# PS_DDR.net
KiCad netlist of a schematic drawn in Altium Designer
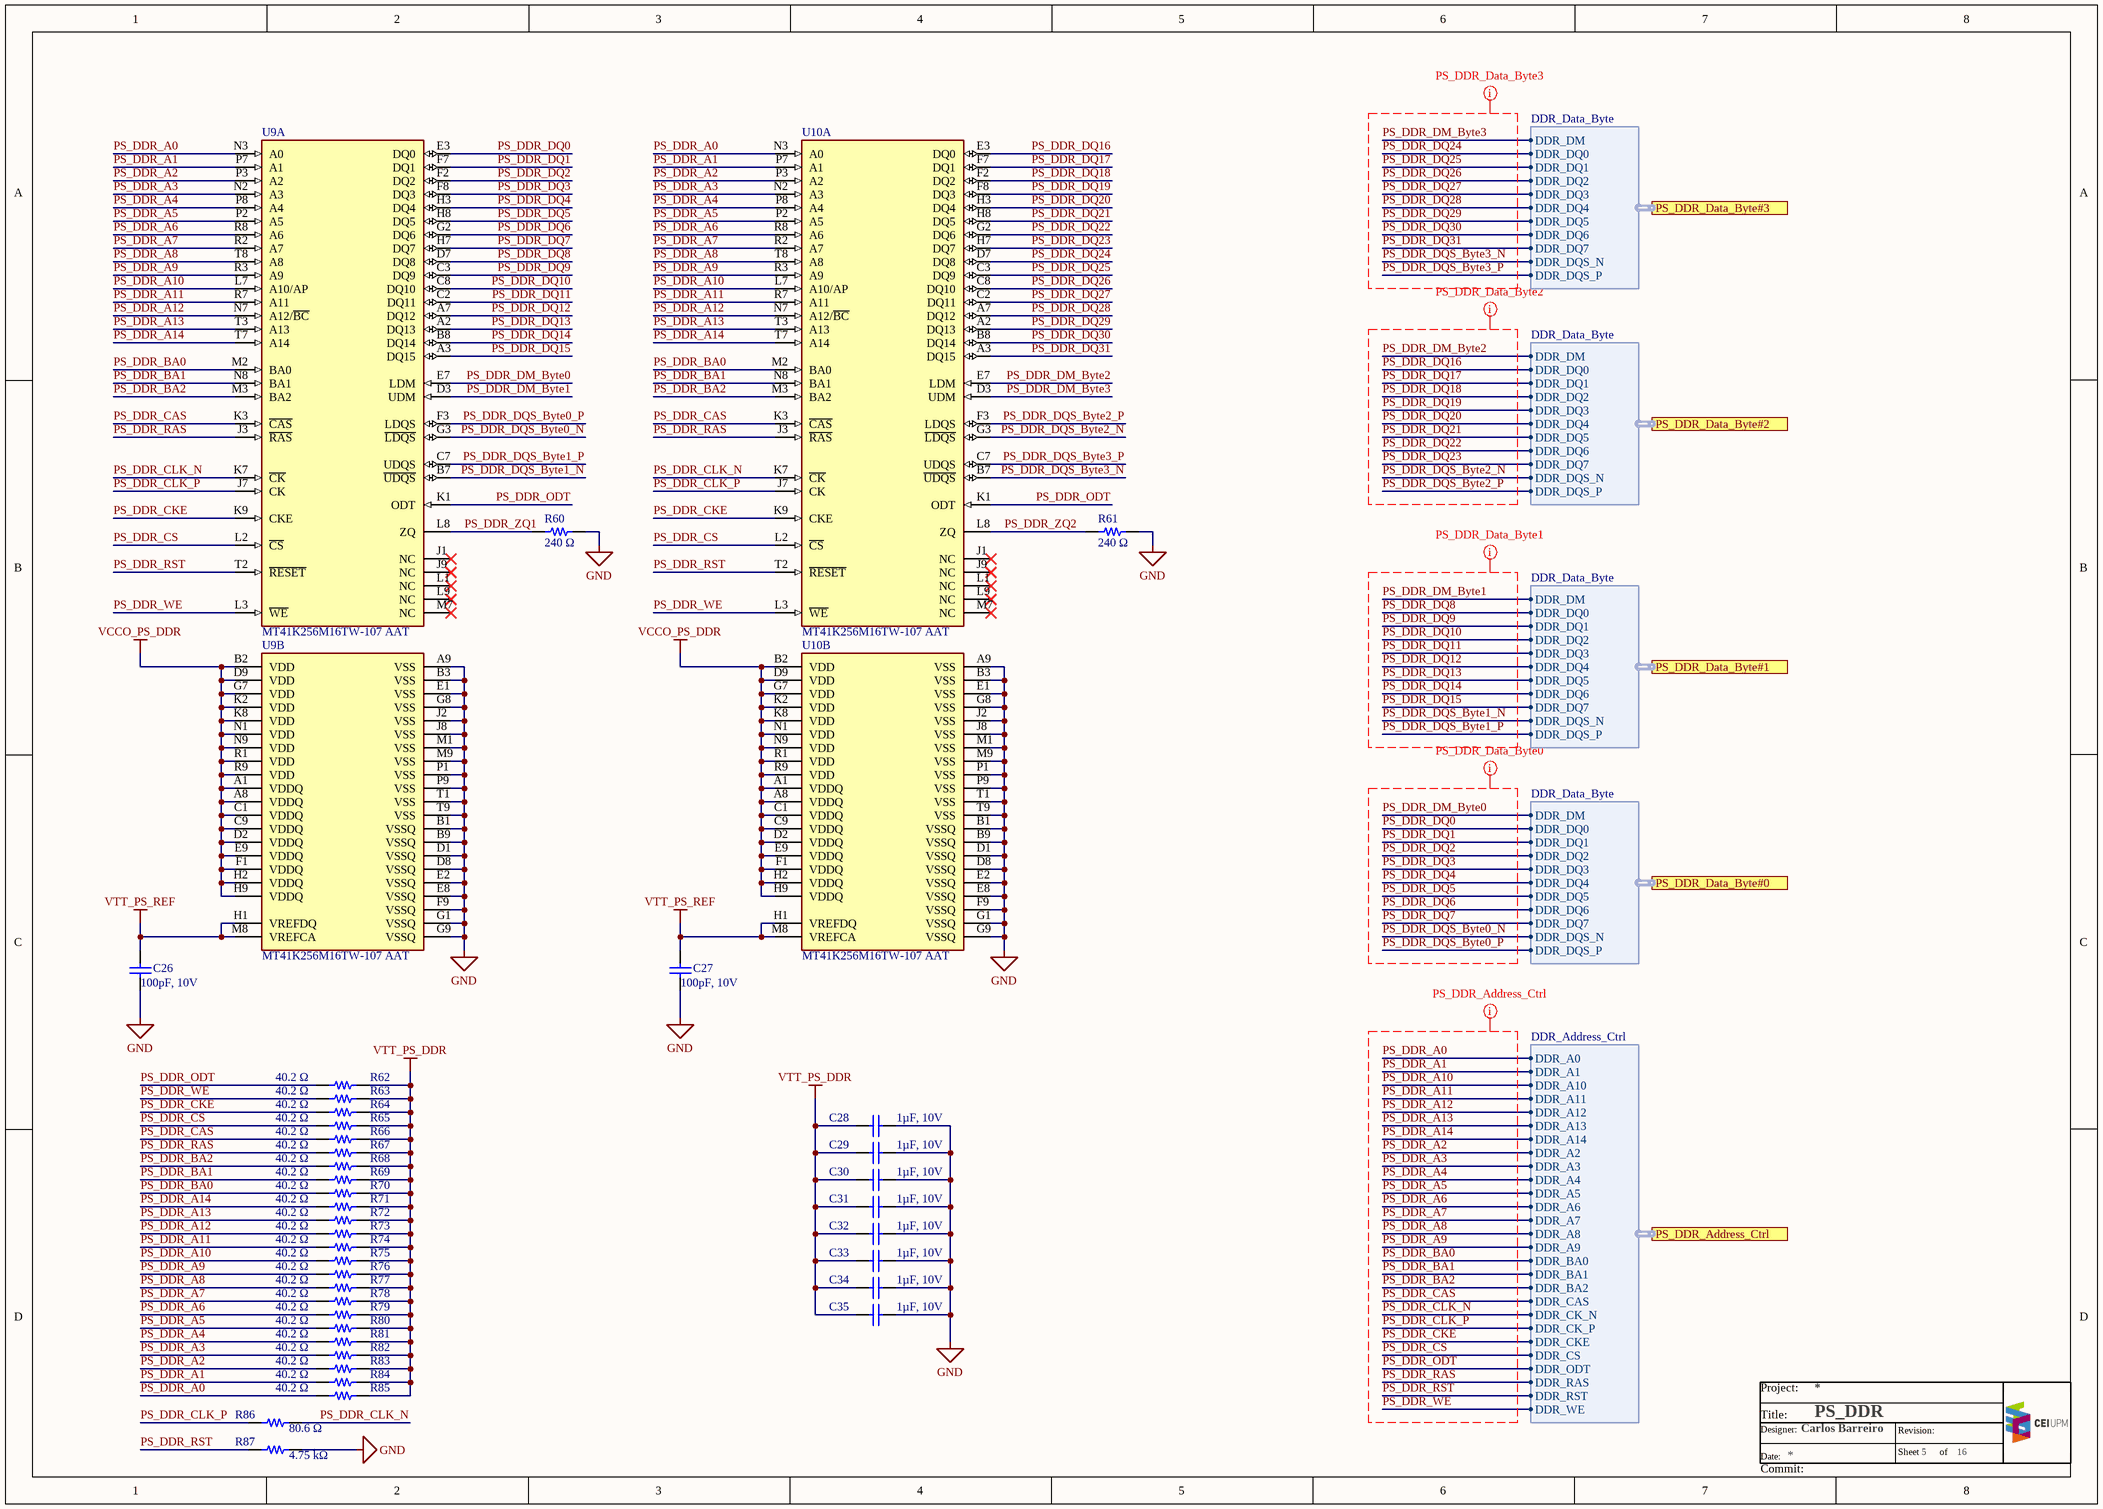
[diagram p0: PS_DDR.SchDoc]

(export (version "E")
  (design (tool "Eeschema 10.0.6"))
  (components
    (comp (ref "C26")
      (value "100pF, 10V")
      (footprint "WURTH_WCAP-CSGP_0402")
      (description "WCAP-CSGP Multilayer Ceramic Chip Capacitor, General Purpose, size 0402, NP0, 100pF, 10V")
      (fields
        (field (name "MANUFACTURER PART NUMBER") "885012005013")
        (field (name "MANUFACTURER") "Wurth Elektronik")
      )
      (libsource (lib "SpaceVNXBaseBoard") (part "885012005013"))
    )
    (comp (ref "C27")
      (value "100pF, 10V")
      (footprint "WURTH_WCAP-CSGP_0402")
      (description "WCAP-CSGP Multilayer Ceramic Chip Capacitor, General Purpose, size 0402, NP0, 100pF, 10V")
      (fields
        (field (name "MANUFACTURER PART NUMBER") "885012005013")
        (field (name "MANUFACTURER") "Wurth Elektronik")
      )
      (libsource (lib "SpaceVNXBaseBoard") (part "885012005013"))
    )
    (comp (ref "C28")
      (value "1µF, 10V")
      (footprint "WURTH_WCAP-CSGP_0402")
      (description "WCAP-CSGP Multilayer Ceramic Chip Capacitor, General Purpose, size 0402, X5R, 1uF, 10V")
      (fields
        (field (name "MANUFACTURER PART NUMBER") "885012105012")
        (field (name "MANUFACTURER") "Wurth Elektronik")
      )
      (libsource (lib "SpaceVNXBaseBoard") (part "885012105012"))
    )
    (comp (ref "C29")
      (value "1µF, 10V")
      (footprint "WURTH_WCAP-CSGP_0402")
      (description "WCAP-CSGP Multilayer Ceramic Chip Capacitor, General Purpose, size 0402, X5R, 1uF, 10V")
      (fields
        (field (name "MANUFACTURER PART NUMBER") "885012105012")
        (field (name "MANUFACTURER") "Wurth Elektronik")
      )
      (libsource (lib "SpaceVNXBaseBoard") (part "885012105012"))
    )
    (comp (ref "C30")
      (value "1µF, 10V")
      (footprint "WURTH_WCAP-CSGP_0402")
      (description "WCAP-CSGP Multilayer Ceramic Chip Capacitor, General Purpose, size 0402, X5R, 1uF, 10V")
      (fields
        (field (name "MANUFACTURER PART NUMBER") "885012105012")
        (field (name "MANUFACTURER") "Wurth Elektronik")
      )
      (libsource (lib "SpaceVNXBaseBoard") (part "885012105012"))
    )
    (comp (ref "C31")
      (value "1µF, 10V")
      (footprint "WURTH_WCAP-CSGP_0402")
      (description "WCAP-CSGP Multilayer Ceramic Chip Capacitor, General Purpose, size 0402, X5R, 1uF, 10V")
      (fields
        (field (name "MANUFACTURER PART NUMBER") "885012105012")
        (field (name "MANUFACTURER") "Wurth Elektronik")
      )
      (libsource (lib "SpaceVNXBaseBoard") (part "885012105012"))
    )
    (comp (ref "C32")
      (value "1µF, 10V")
      (footprint "WURTH_WCAP-CSGP_0402")
      (description "WCAP-CSGP Multilayer Ceramic Chip Capacitor, General Purpose, size 0402, X5R, 1uF, 10V")
      (fields
        (field (name "MANUFACTURER PART NUMBER") "885012105012")
        (field (name "MANUFACTURER") "Wurth Elektronik")
      )
      (libsource (lib "SpaceVNXBaseBoard") (part "885012105012"))
    )
    (comp (ref "C33")
      (value "1µF, 10V")
      (footprint "WURTH_WCAP-CSGP_0402")
      (description "WCAP-CSGP Multilayer Ceramic Chip Capacitor, General Purpose, size 0402, X5R, 1uF, 10V")
      (fields
        (field (name "MANUFACTURER PART NUMBER") "885012105012")
        (field (name "MANUFACTURER") "Wurth Elektronik")
      )
      (libsource (lib "SpaceVNXBaseBoard") (part "885012105012"))
    )
    (comp (ref "C34")
      (value "1µF, 10V")
      (footprint "WURTH_WCAP-CSGP_0402")
      (description "WCAP-CSGP Multilayer Ceramic Chip Capacitor, General Purpose, size 0402, X5R, 1uF, 10V")
      (fields
        (field (name "MANUFACTURER PART NUMBER") "885012105012")
        (field (name "MANUFACTURER") "Wurth Elektronik")
      )
      (libsource (lib "SpaceVNXBaseBoard") (part "885012105012"))
    )
    (comp (ref "C35")
      (value "1µF, 10V")
      (footprint "WURTH_WCAP-CSGP_0402")
      (description "WCAP-CSGP Multilayer Ceramic Chip Capacitor, General Purpose, size 0402, X5R, 1uF, 10V")
      (fields
        (field (name "MANUFACTURER PART NUMBER") "885012105012")
        (field (name "MANUFACTURER") "Wurth Elektronik")
      )
      (libsource (lib "SpaceVNXBaseBoard") (part "885012105012"))
    )
    (comp (ref "R60")
      (value "240 Ω")
      (footprint "PANASONIC_ERJ2G_0402")
      (description "General Purpose Thick Film Chip Resistors")
      (fields (field (name "MANUFACTURER") "Panasonic"))
      (libsource (lib "SpaceVNXBaseBoard") (part "ERJ2GEJ241X"))
    )
    (comp (ref "R61")
      (value "240 Ω")
      (footprint "PANASONIC_ERJ2G_0402")
      (description "General Purpose Thick Film Chip Resistors")
      (fields (field (name "MANUFACTURER") "Panasonic"))
      (libsource (lib "SpaceVNXBaseBoard") (part "ERJ2GEJ241X"))
    )
    (comp (ref "R62")
      (value "40.2 Ω")
      (footprint "PANASONIC_ERJ2G_0402")
      (description "General Purpose Thick Film Chip Resistors")
      (fields (field (name "MANUFACTURER") "Panasonic"))
      (libsource (lib "SpaceVNXBaseBoard") (part "ERJ2RKF40R2X"))
    )
    (comp (ref "R63")
      (value "40.2 Ω")
      (footprint "PANASONIC_ERJ2G_0402")
      (description "General Purpose Thick Film Chip Resistors")
      (fields (field (name "MANUFACTURER") "Panasonic"))
      (libsource (lib "SpaceVNXBaseBoard") (part "ERJ2RKF40R2X"))
    )
    (comp (ref "R64")
      (value "40.2 Ω")
      (footprint "PANASONIC_ERJ2G_0402")
      (description "General Purpose Thick Film Chip Resistors")
      (fields (field (name "MANUFACTURER") "Panasonic"))
      (libsource (lib "SpaceVNXBaseBoard") (part "ERJ2RKF40R2X"))
    )
    (comp (ref "R65")
      (value "40.2 Ω")
      (footprint "PANASONIC_ERJ2G_0402")
      (description "General Purpose Thick Film Chip Resistors")
      (fields (field (name "MANUFACTURER") "Panasonic"))
      (libsource (lib "SpaceVNXBaseBoard") (part "ERJ2RKF40R2X"))
    )
    (comp (ref "R66")
      (value "40.2 Ω")
      (footprint "PANASONIC_ERJ2G_0402")
      (description "General Purpose Thick Film Chip Resistors")
      (fields (field (name "MANUFACTURER") "Panasonic"))
      (libsource (lib "SpaceVNXBaseBoard") (part "ERJ2RKF40R2X"))
    )
    (comp (ref "R67")
      (value "40.2 Ω")
      (footprint "PANASONIC_ERJ2G_0402")
      (description "General Purpose Thick Film Chip Resistors")
      (fields (field (name "MANUFACTURER") "Panasonic"))
      (libsource (lib "SpaceVNXBaseBoard") (part "ERJ2RKF40R2X"))
    )
    (comp (ref "R68")
      (value "40.2 Ω")
      (footprint "PANASONIC_ERJ2G_0402")
      (description "General Purpose Thick Film Chip Resistors")
      (fields (field (name "MANUFACTURER") "Panasonic"))
      (libsource (lib "SpaceVNXBaseBoard") (part "ERJ2RKF40R2X"))
    )
    (comp (ref "R69")
      (value "40.2 Ω")
      (footprint "PANASONIC_ERJ2G_0402")
      (description "General Purpose Thick Film Chip Resistors")
      (fields (field (name "MANUFACTURER") "Panasonic"))
      (libsource (lib "SpaceVNXBaseBoard") (part "ERJ2RKF40R2X"))
    )
    (comp (ref "R70")
      (value "40.2 Ω")
      (footprint "PANASONIC_ERJ2G_0402")
      (description "General Purpose Thick Film Chip Resistors")
      (fields (field (name "MANUFACTURER") "Panasonic"))
      (libsource (lib "SpaceVNXBaseBoard") (part "ERJ2RKF40R2X"))
    )
    (comp (ref "R71")
      (value "40.2 Ω")
      (footprint "PANASONIC_ERJ2G_0402")
      (description "General Purpose Thick Film Chip Resistors")
      (fields (field (name "MANUFACTURER") "Panasonic"))
      (libsource (lib "SpaceVNXBaseBoard") (part "ERJ2RKF40R2X"))
    )
    (comp (ref "R72")
      (value "40.2 Ω")
      (footprint "PANASONIC_ERJ2G_0402")
      (description "General Purpose Thick Film Chip Resistors")
      (fields (field (name "MANUFACTURER") "Panasonic"))
      (libsource (lib "SpaceVNXBaseBoard") (part "ERJ2RKF40R2X"))
    )
    (comp (ref "R73")
      (value "40.2 Ω")
      (footprint "PANASONIC_ERJ2G_0402")
      (description "General Purpose Thick Film Chip Resistors")
      (fields (field (name "MANUFACTURER") "Panasonic"))
      (libsource (lib "SpaceVNXBaseBoard") (part "ERJ2RKF40R2X"))
    )
    (comp (ref "R74")
      (value "40.2 Ω")
      (footprint "PANASONIC_ERJ2G_0402")
      (description "General Purpose Thick Film Chip Resistors")
      (fields (field (name "MANUFACTURER") "Panasonic"))
      (libsource (lib "SpaceVNXBaseBoard") (part "ERJ2RKF40R2X"))
    )
    (comp (ref "R75")
      (value "40.2 Ω")
      (footprint "PANASONIC_ERJ2G_0402")
      (description "General Purpose Thick Film Chip Resistors")
      (fields (field (name "MANUFACTURER") "Panasonic"))
      (libsource (lib "SpaceVNXBaseBoard") (part "ERJ2RKF40R2X"))
    )
    (comp (ref "R76")
      (value "40.2 Ω")
      (footprint "PANASONIC_ERJ2G_0402")
      (description "General Purpose Thick Film Chip Resistors")
      (fields (field (name "MANUFACTURER") "Panasonic"))
      (libsource (lib "SpaceVNXBaseBoard") (part "ERJ2RKF40R2X"))
    )
    (comp (ref "R77")
      (value "40.2 Ω")
      (footprint "PANASONIC_ERJ2G_0402")
      (description "General Purpose Thick Film Chip Resistors")
      (fields (field (name "MANUFACTURER") "Panasonic"))
      (libsource (lib "SpaceVNXBaseBoard") (part "ERJ2RKF40R2X"))
    )
    (comp (ref "R78")
      (value "40.2 Ω")
      (footprint "PANASONIC_ERJ2G_0402")
      (description "General Purpose Thick Film Chip Resistors")
      (fields (field (name "MANUFACTURER") "Panasonic"))
      (libsource (lib "SpaceVNXBaseBoard") (part "ERJ2RKF40R2X"))
    )
    (comp (ref "R79")
      (value "40.2 Ω")
      (footprint "PANASONIC_ERJ2G_0402")
      (description "General Purpose Thick Film Chip Resistors")
      (fields (field (name "MANUFACTURER") "Panasonic"))
      (libsource (lib "SpaceVNXBaseBoard") (part "ERJ2RKF40R2X"))
    )
    (comp (ref "R80")
      (value "40.2 Ω")
      (footprint "PANASONIC_ERJ2G_0402")
      (description "General Purpose Thick Film Chip Resistors")
      (fields (field (name "MANUFACTURER") "Panasonic"))
      (libsource (lib "SpaceVNXBaseBoard") (part "ERJ2RKF40R2X"))
    )
    (comp (ref "R81")
      (value "40.2 Ω")
      (footprint "PANASONIC_ERJ2G_0402")
      (description "General Purpose Thick Film Chip Resistors")
      (fields (field (name "MANUFACTURER") "Panasonic"))
      (libsource (lib "SpaceVNXBaseBoard") (part "ERJ2RKF40R2X"))
    )
    (comp (ref "R82")
      (value "40.2 Ω")
      (footprint "PANASONIC_ERJ2G_0402")
      (description "General Purpose Thick Film Chip Resistors")
      (fields (field (name "MANUFACTURER") "Panasonic"))
      (libsource (lib "SpaceVNXBaseBoard") (part "ERJ2RKF40R2X"))
    )
    (comp (ref "R83")
      (value "40.2 Ω")
      (footprint "PANASONIC_ERJ2G_0402")
      (description "General Purpose Thick Film Chip Resistors")
      (fields (field (name "MANUFACTURER") "Panasonic"))
      (libsource (lib "SpaceVNXBaseBoard") (part "ERJ2RKF40R2X"))
    )
    (comp (ref "R84")
      (value "40.2 Ω")
      (footprint "PANASONIC_ERJ2G_0402")
      (description "General Purpose Thick Film Chip Resistors")
      (fields (field (name "MANUFACTURER") "Panasonic"))
      (libsource (lib "SpaceVNXBaseBoard") (part "ERJ2RKF40R2X"))
    )
    (comp (ref "R85")
      (value "40.2 Ω")
      (footprint "PANASONIC_ERJ2G_0402")
      (description "General Purpose Thick Film Chip Resistors")
      (fields (field (name "MANUFACTURER") "Panasonic"))
      (libsource (lib "SpaceVNXBaseBoard") (part "ERJ2RKF40R2X"))
    )
    (comp (ref "R86")
      (value "80.6 Ω")
      (footprint "PANASONIC_ERJ2G_0402")
      (description "General Purpose Thick Film Chip Resistors")
      (fields (field (name "MANUFACTURER") "Panasonic"))
      (libsource (lib "SpaceVNXBaseBoard") (part "ERJ2RKF80R6X"))
    )
    (comp (ref "R87")
      (value "4.75 kΩ")
      (footprint "PANASONIC_ERJ2G_0402")
      (description "General Purpose Thick Film Chip Resistors")
      (fields (field (name "MANUFACTURER") "Panasonic"))
      (libsource (lib "SpaceVNXBaseBoard") (part "ERJ2RKF4751X"))
    )
    (comp (ref "U9")
      (value "MT41K256M16TW-107 AAT")
      (footprint "Micron_TW")
      (description "DDR3L SDRAM")
      (libsource (lib "SpaceVNXBaseBoard") (part "MT41K256M16TW-107 AAT"))
    )
    (comp (ref "U10")
      (value "MT41K256M16TW-107 AAT")
      (footprint "Micron_TW")
      (description "DDR3L SDRAM")
      (libsource (lib "SpaceVNXBaseBoard") (part "MT41K256M16TW-107 AAT"))
    )
  )
  (nets
    (net (code "3") (name "/PS_DDR_A0") (class "Default")
      (node (ref "R85") (pin "2") (pinfunction "2_2") (pintype "passive"))
      (node (ref "U10") (pin "N3") (pinfunction "A0_N3") (pintype "input"))
      (node (ref "U9") (pin "N3") (pinfunction "A0_N3") (pintype "input"))
    )
    (net (code "4") (name "/PS_DDR_A1") (class "Default")
      (node (ref "R84") (pin "2") (pinfunction "2_2") (pintype "passive"))
      (node (ref "U10") (pin "P7") (pinfunction "A1_P7") (pintype "input"))
      (node (ref "U9") (pin "P7") (pinfunction "A1_P7") (pintype "input"))
    )
    (net (code "5") (name "/PS_DDR_A2") (class "Default")
      (node (ref "R83") (pin "2") (pinfunction "2_2") (pintype "passive"))
      (node (ref "U10") (pin "P3") (pinfunction "A2_P3") (pintype "input"))
      (node (ref "U9") (pin "P3") (pinfunction "A2_P3") (pintype "input"))
    )
    (net (code "6") (name "/PS_DDR_A3") (class "Default")
      (node (ref "R82") (pin "2") (pinfunction "2_2") (pintype "passive"))
      (node (ref "U10") (pin "N2") (pinfunction "A3_N2") (pintype "input"))
      (node (ref "U9") (pin "N2") (pinfunction "A3_N2") (pintype "input"))
    )
    (net (code "7") (name "/PS_DDR_A4") (class "Default")
      (node (ref "R81") (pin "2") (pinfunction "2_2") (pintype "passive"))
      (node (ref "U10") (pin "P8") (pinfunction "A4_P8") (pintype "input"))
      (node (ref "U9") (pin "P8") (pinfunction "A4_P8") (pintype "input"))
    )
    (net (code "8") (name "/PS_DDR_A5") (class "Default")
      (node (ref "R80") (pin "2") (pinfunction "2_2") (pintype "passive"))
      (node (ref "U10") (pin "P2") (pinfunction "A5_P2") (pintype "input"))
      (node (ref "U9") (pin "P2") (pinfunction "A5_P2") (pintype "input"))
    )
    (net (code "9") (name "/PS_DDR_A6") (class "Default")
      (node (ref "R79") (pin "2") (pinfunction "2_2") (pintype "passive"))
      (node (ref "U10") (pin "R8") (pinfunction "A6_R8") (pintype "input"))
      (node (ref "U9") (pin "R8") (pinfunction "A6_R8") (pintype "input"))
    )
    (net (code "10") (name "/PS_DDR_A7") (class "Default")
      (node (ref "R78") (pin "2") (pinfunction "2_2") (pintype "passive"))
      (node (ref "U10") (pin "R2") (pinfunction "A7_R2") (pintype "input"))
      (node (ref "U9") (pin "R2") (pinfunction "A7_R2") (pintype "input"))
    )
    (net (code "11") (name "/PS_DDR_A8") (class "Default")
      (node (ref "R77") (pin "2") (pinfunction "2_2") (pintype "passive"))
      (node (ref "U10") (pin "T8") (pinfunction "A8_T8") (pintype "input"))
      (node (ref "U9") (pin "T8") (pinfunction "A8_T8") (pintype "input"))
    )
    (net (code "12") (name "/PS_DDR_A9") (class "Default")
      (node (ref "R76") (pin "2") (pinfunction "2_2") (pintype "passive"))
      (node (ref "U10") (pin "R3") (pinfunction "A9_R3") (pintype "input"))
      (node (ref "U9") (pin "R3") (pinfunction "A9_R3") (pintype "input"))
    )
    (net (code "13") (name "/PS_DDR_A10") (class "Default")
      (node (ref "R75") (pin "2") (pinfunction "2_2") (pintype "passive"))
      (node (ref "U10") (pin "L7") (pinfunction "A10/AP_L7") (pintype "input"))
      (node (ref "U9") (pin "L7") (pinfunction "A10/AP_L7") (pintype "input"))
    )
    (net (code "14") (name "/PS_DDR_A11") (class "Default")
      (node (ref "R74") (pin "2") (pinfunction "2_2") (pintype "passive"))
      (node (ref "U10") (pin "R7") (pinfunction "A11_R7") (pintype "input"))
      (node (ref "U9") (pin "R7") (pinfunction "A11_R7") (pintype "input"))
    )
    (net (code "15") (name "/PS_DDR_A12") (class "Default")
      (node (ref "R73") (pin "2") (pinfunction "2_2") (pintype "passive"))
      (node (ref "U10") (pin "N7") (pinfunction "A12/~{BC}_N7") (pintype "input"))
      (node (ref "U9") (pin "N7") (pinfunction "A12/~{BC}_N7") (pintype "input"))
    )
    (net (code "16") (name "/PS_DDR_A13") (class "Default")
      (node (ref "R72") (pin "2") (pinfunction "2_2") (pintype "passive"))
      (node (ref "U10") (pin "T3") (pinfunction "A13_T3") (pintype "input"))
      (node (ref "U9") (pin "T3") (pinfunction "A13_T3") (pintype "input"))
    )
    (net (code "17") (name "/PS_DDR_A14") (class "Default")
      (node (ref "R71") (pin "2") (pinfunction "2_2") (pintype "passive"))
      (node (ref "U10") (pin "T7") (pinfunction "A14_T7") (pintype "input"))
      (node (ref "U9") (pin "T7") (pinfunction "A14_T7") (pintype "input"))
    )
    (net (code "18") (name "/PS_DDR_BA0") (class "Default")
      (node (ref "R70") (pin "2") (pinfunction "2_2") (pintype "passive"))
      (node (ref "U10") (pin "M2") (pinfunction "BA0_M2") (pintype "input"))
      (node (ref "U9") (pin "M2") (pinfunction "BA0_M2") (pintype "input"))
    )
    (net (code "19") (name "/PS_DDR_BA1") (class "Default")
      (node (ref "R69") (pin "2") (pinfunction "2_2") (pintype "passive"))
      (node (ref "U10") (pin "N8") (pinfunction "BA1_N8") (pintype "input"))
      (node (ref "U9") (pin "N8") (pinfunction "BA1_N8") (pintype "input"))
    )
    (net (code "20") (name "/PS_DDR_BA2") (class "Default")
      (node (ref "R68") (pin "2") (pinfunction "2_2") (pintype "passive"))
      (node (ref "U10") (pin "M3") (pinfunction "BA2_M3") (pintype "input"))
      (node (ref "U9") (pin "M3") (pinfunction "BA2_M3") (pintype "input"))
    )
    (net (code "21") (name "/PS_DDR_CAS") (class "Default")
      (node (ref "R66") (pin "2") (pinfunction "2_2") (pintype "passive"))
      (node (ref "U10") (pin "K3") (pinfunction "~{CAS}_K3") (pintype "input"))
      (node (ref "U9") (pin "K3") (pinfunction "~{CAS}_K3") (pintype "input"))
    )
    (net (code "22") (name "/PS_DDR_CKE") (class "Default")
      (node (ref "R64") (pin "2") (pinfunction "2_2") (pintype "passive"))
      (node (ref "U10") (pin "K9") (pinfunction "CKE_K9") (pintype "input"))
      (node (ref "U9") (pin "K9") (pinfunction "CKE_K9") (pintype "input"))
    )
    (net (code "23") (name "/PS_DDR_CLK_N") (class "Default")
      (node (ref "R86") (pin "2") (pinfunction "2_2") (pintype "passive"))
      (node (ref "U10") (pin "K7") (pinfunction "~{CK}_K7") (pintype "input"))
      (node (ref "U9") (pin "K7") (pinfunction "~{CK}_K7") (pintype "input"))
    )
    (net (code "24") (name "/PS_DDR_CLK_P") (class "Default")
      (node (ref "R86") (pin "1") (pinfunction "1_1") (pintype "passive"))
      (node (ref "U10") (pin "J7") (pinfunction "CK_J7") (pintype "input"))
      (node (ref "U9") (pin "J7") (pinfunction "CK_J7") (pintype "input"))
    )
    (net (code "25") (name "/PS_DDR_CS") (class "Default")
      (node (ref "R65") (pin "2") (pinfunction "2_2") (pintype "passive"))
      (node (ref "U10") (pin "L2") (pinfunction "~{CS}_L2") (pintype "input"))
      (node (ref "U9") (pin "L2") (pinfunction "~{CS}_L2") (pintype "input"))
    )
    (net (code "26") (name "/PS_DDR_DM_Byte0") (class "Default")
      (node (ref "U9") (pin "E7") (pinfunction "LDM_E7") (pintype "input"))
    )
    (net (code "27") (name "/PS_DDR_DM_Byte1") (class "Default")
      (node (ref "U9") (pin "D3") (pinfunction "UDM_D3") (pintype "input"))
    )
    (net (code "28") (name "/PS_DDR_DM_Byte2") (class "Default")
      (node (ref "U10") (pin "E7") (pinfunction "LDM_E7") (pintype "input"))
    )
    (net (code "29") (name "/PS_DDR_DM_Byte3") (class "Default")
      (node (ref "U10") (pin "D3") (pinfunction "UDM_D3") (pintype "input"))
    )
    (net (code "30") (name "/PS_DDR_DQ0") (class "Default")
      (node (ref "U9") (pin "E3") (pinfunction "DQ0_E3") (pintype "bidirectional"))
    )
    (net (code "31") (name "/PS_DDR_DQ1") (class "Default")
      (node (ref "U9") (pin "F7") (pinfunction "DQ1_F7") (pintype "bidirectional"))
    )
    (net (code "32") (name "/PS_DDR_DQ2") (class "Default")
      (node (ref "U9") (pin "F2") (pinfunction "DQ2_F2") (pintype "bidirectional"))
    )
    (net (code "33") (name "/PS_DDR_DQ3") (class "Default")
      (node (ref "U9") (pin "F8") (pinfunction "DQ3_F8") (pintype "bidirectional"))
    )
    (net (code "34") (name "/PS_DDR_DQ4") (class "Default")
      (node (ref "U9") (pin "H3") (pinfunction "DQ4_H3") (pintype "bidirectional"))
    )
    (net (code "35") (name "/PS_DDR_DQ5") (class "Default")
      (node (ref "U9") (pin "H8") (pinfunction "DQ5_H8") (pintype "bidirectional"))
    )
    (net (code "36") (name "/PS_DDR_DQ6") (class "Default")
      (node (ref "U9") (pin "G2") (pinfunction "DQ6_G2") (pintype "bidirectional"))
    )
    (net (code "37") (name "/PS_DDR_DQ7") (class "Default")
      (node (ref "U9") (pin "H7") (pinfunction "DQ7_H7") (pintype "bidirectional"))
    )
    (net (code "38") (name "/PS_DDR_DQ8") (class "Default")
      (node (ref "U9") (pin "D7") (pinfunction "DQ8_D7") (pintype "bidirectional"))
    )
    (net (code "39") (name "/PS_DDR_DQ9") (class "Default")
      (node (ref "U9") (pin "C3") (pinfunction "DQ9_C3") (pintype "bidirectional"))
    )
    (net (code "40") (name "/PS_DDR_DQ10") (class "Default")
      (node (ref "U9") (pin "C8") (pinfunction "DQ10_C8") (pintype "bidirectional"))
    )
    (net (code "41") (name "/PS_DDR_DQ11") (class "Default")
      (node (ref "U9") (pin "C2") (pinfunction "DQ11_C2") (pintype "bidirectional"))
    )
    (net (code "42") (name "/PS_DDR_DQ12") (class "Default")
      (node (ref "U9") (pin "A7") (pinfunction "DQ12_A7") (pintype "bidirectional"))
    )
    (net (code "43") (name "/PS_DDR_DQ13") (class "Default")
      (node (ref "U9") (pin "A2") (pinfunction "DQ13_A2") (pintype "bidirectional"))
    )
    (net (code "44") (name "/PS_DDR_DQ14") (class "Default")
      (node (ref "U9") (pin "B8") (pinfunction "DQ14_B8") (pintype "bidirectional"))
    )
    (net (code "45") (name "/PS_DDR_DQ15") (class "Default")
      (node (ref "U9") (pin "A3") (pinfunction "DQ15_A3") (pintype "bidirectional"))
    )
    (net (code "46") (name "/PS_DDR_DQ16") (class "Default")
      (node (ref "U10") (pin "E3") (pinfunction "DQ0_E3") (pintype "bidirectional"))
    )
    (net (code "47") (name "/PS_DDR_DQ17") (class "Default")
      (node (ref "U10") (pin "F7") (pinfunction "DQ1_F7") (pintype "bidirectional"))
    )
    (net (code "48") (name "/PS_DDR_DQ18") (class "Default")
      (node (ref "U10") (pin "F2") (pinfunction "DQ2_F2") (pintype "bidirectional"))
    )
    (net (code "49") (name "/PS_DDR_DQ19") (class "Default")
      (node (ref "U10") (pin "F8") (pinfunction "DQ3_F8") (pintype "bidirectional"))
    )
    (net (code "50") (name "/PS_DDR_DQ20") (class "Default")
      (node (ref "U10") (pin "H3") (pinfunction "DQ4_H3") (pintype "bidirectional"))
    )
    (net (code "51") (name "/PS_DDR_DQ21") (class "Default")
      (node (ref "U10") (pin "H8") (pinfunction "DQ5_H8") (pintype "bidirectional"))
    )
    (net (code "52") (name "/PS_DDR_DQ22") (class "Default")
      (node (ref "U10") (pin "G2") (pinfunction "DQ6_G2") (pintype "bidirectional"))
    )
    (net (code "53") (name "/PS_DDR_DQ23") (class "Default")
      (node (ref "U10") (pin "H7") (pinfunction "DQ7_H7") (pintype "bidirectional"))
    )
    (net (code "54") (name "/PS_DDR_DQ24") (class "Default")
      (node (ref "U10") (pin "D7") (pinfunction "DQ8_D7") (pintype "bidirectional"))
    )
    (net (code "55") (name "/PS_DDR_DQ25") (class "Default")
      (node (ref "U10") (pin "C3") (pinfunction "DQ9_C3") (pintype "bidirectional"))
    )
    (net (code "56") (name "/PS_DDR_DQ26") (class "Default")
      (node (ref "U10") (pin "C8") (pinfunction "DQ10_C8") (pintype "bidirectional"))
    )
    (net (code "57") (name "/PS_DDR_DQ27") (class "Default")
      (node (ref "U10") (pin "C2") (pinfunction "DQ11_C2") (pintype "bidirectional"))
    )
    (net (code "58") (name "/PS_DDR_DQ28") (class "Default")
      (node (ref "U10") (pin "A7") (pinfunction "DQ12_A7") (pintype "bidirectional"))
    )
    (net (code "59") (name "/PS_DDR_DQ29") (class "Default")
      (node (ref "U10") (pin "A2") (pinfunction "DQ13_A2") (pintype "bidirectional"))
    )
    (net (code "60") (name "/PS_DDR_DQ30") (class "Default")
      (node (ref "U10") (pin "B8") (pinfunction "DQ14_B8") (pintype "bidirectional"))
    )
    (net (code "61") (name "/PS_DDR_DQ31") (class "Default")
      (node (ref "U10") (pin "A3") (pinfunction "DQ15_A3") (pintype "bidirectional"))
    )
    (net (code "62") (name "/PS_DDR_DQS_Byte0_N") (class "Default")
      (node (ref "U9") (pin "G3") (pinfunction "~{LDQS}_G3") (pintype "bidirectional"))
    )
    (net (code "63") (name "/PS_DDR_DQS_Byte0_P") (class "Default")
      (node (ref "U9") (pin "F3") (pinfunction "LDQS_F3") (pintype "bidirectional"))
    )
    (net (code "64") (name "/PS_DDR_DQS_Byte1_N") (class "Default")
      (node (ref "U9") (pin "B7") (pinfunction "~{UDQS}_B7") (pintype "bidirectional"))
    )
    (net (code "65") (name "/PS_DDR_DQS_Byte1_P") (class "Default")
      (node (ref "U9") (pin "C7") (pinfunction "UDQS_C7") (pintype "bidirectional"))
    )
    (net (code "66") (name "/PS_DDR_DQS_Byte2_N") (class "Default")
      (node (ref "U10") (pin "G3") (pinfunction "~{LDQS}_G3") (pintype "bidirectional"))
    )
    (net (code "67") (name "/PS_DDR_DQS_Byte2_P") (class "Default")
      (node (ref "U10") (pin "F3") (pinfunction "LDQS_F3") (pintype "bidirectional"))
    )
    (net (code "68") (name "/PS_DDR_DQS_Byte3_N") (class "Default")
      (node (ref "U10") (pin "B7") (pinfunction "~{UDQS}_B7") (pintype "bidirectional"))
    )
    (net (code "69") (name "/PS_DDR_DQS_Byte3_P") (class "Default")
      (node (ref "U10") (pin "C7") (pinfunction "UDQS_C7") (pintype "bidirectional"))
    )
    (net (code "70") (name "/PS_DDR_ODT") (class "Default")
      (node (ref "R62") (pin "2") (pinfunction "2_2") (pintype "passive"))
      (node (ref "U10") (pin "K1") (pinfunction "ODT_K1") (pintype "input"))
      (node (ref "U9") (pin "K1") (pinfunction "ODT_K1") (pintype "input"))
    )
    (net (code "71") (name "/PS_DDR_RAS") (class "Default")
      (node (ref "R67") (pin "2") (pinfunction "2_2") (pintype "passive"))
      (node (ref "U10") (pin "J3") (pinfunction "~{RAS}_J3") (pintype "input"))
      (node (ref "U9") (pin "J3") (pinfunction "~{RAS}_J3") (pintype "input"))
    )
    (net (code "72") (name "/PS_DDR_RST") (class "Default")
      (node (ref "R87") (pin "1") (pinfunction "1_1") (pintype "passive"))
      (node (ref "U10") (pin "T2") (pinfunction "~{RESET}_T2") (pintype "input"))
      (node (ref "U9") (pin "T2") (pinfunction "~{RESET}_T2") (pintype "input"))
    )
    (net (code "73") (name "/PS_DDR_WE") (class "Default")
      (node (ref "R63") (pin "2") (pinfunction "2_2") (pintype "passive"))
      (node (ref "U10") (pin "L3") (pinfunction "~{WE}_L3") (pintype "input"))
      (node (ref "U9") (pin "L3") (pinfunction "~{WE}_L3") (pintype "input"))
    )
    (net (code "74") (name "/PS_DDR_ZQ1") (class "Default")
      (node (ref "R60") (pin "1") (pinfunction "1_1") (pintype "passive"))
      (node (ref "U9") (pin "L8") (pinfunction "ZQ_L8") (pintype "passive"))
    )
    (net (code "75") (name "/PS_DDR_ZQ2") (class "Default")
      (node (ref "R61") (pin "1") (pinfunction "1_1") (pintype "passive"))
      (node (ref "U10") (pin "L8") (pinfunction "ZQ_L8") (pintype "passive"))
    )
    (net (code "78") (name "GND") (class "Default")
      (node (ref "C26") (pin "1") (pinfunction "1_1") (pintype "passive"))
      (node (ref "C27") (pin "1") (pinfunction "1_1") (pintype "passive"))
      (node (ref "C28") (pin "1") (pinfunction "1_1") (pintype "passive"))
      (node (ref "C29") (pin "1") (pinfunction "1_1") (pintype "passive"))
      (node (ref "C30") (pin "1") (pinfunction "1_1") (pintype "passive"))
      (node (ref "C31") (pin "1") (pinfunction "1_1") (pintype "passive"))
      (node (ref "C32") (pin "1") (pinfunction "1_1") (pintype "passive"))
      (node (ref "C33") (pin "1") (pinfunction "1_1") (pintype "passive"))
      (node (ref "C34") (pin "1") (pinfunction "1_1") (pintype "passive"))
      (node (ref "C35") (pin "1") (pinfunction "1_1") (pintype "passive"))
      (node (ref "R60") (pin "2") (pinfunction "2_2") (pintype "passive"))
      (node (ref "R61") (pin "2") (pinfunction "2_2") (pintype "passive"))
      (node (ref "R87") (pin "2") (pinfunction "2_2") (pintype "passive"))
      (node (ref "U10") (pin "A9") (pinfunction "VSS_A9") (pintype "power_in"))
      (node (ref "U10") (pin "B1") (pinfunction "VSSQ_B1") (pintype "power_in"))
      (node (ref "U10") (pin "B3") (pinfunction "VSS_B3") (pintype "power_in"))
      (node (ref "U10") (pin "B9") (pinfunction "VSSQ_B9") (pintype "power_in"))
      (node (ref "U10") (pin "D1") (pinfunction "VSSQ_D1") (pintype "power_in"))
      (node (ref "U10") (pin "D8") (pinfunction "VSSQ_D8") (pintype "power_in"))
      (node (ref "U10") (pin "E1") (pinfunction "VSS_E1") (pintype "power_in"))
      (node (ref "U10") (pin "E2") (pinfunction "VSSQ_E2") (pintype "power_in"))
      (node (ref "U10") (pin "E8") (pinfunction "VSSQ_E8") (pintype "power_in"))
      (node (ref "U10") (pin "F9") (pinfunction "VSSQ_F9") (pintype "power_in"))
      (node (ref "U10") (pin "G1") (pinfunction "VSSQ_G1") (pintype "power_in"))
      (node (ref "U10") (pin "G8") (pinfunction "VSS_G8") (pintype "power_in"))
      (node (ref "U10") (pin "G9") (pinfunction "VSSQ_G9") (pintype "power_in"))
      (node (ref "U10") (pin "J2") (pinfunction "VSS_J2") (pintype "power_in"))
      (node (ref "U10") (pin "J8") (pinfunction "VSS_J8") (pintype "power_in"))
      (node (ref "U10") (pin "M1") (pinfunction "VSS_M1") (pintype "power_in"))
      (node (ref "U10") (pin "M9") (pinfunction "VSS_M9") (pintype "power_in"))
      (node (ref "U10") (pin "P1") (pinfunction "VSS_P1") (pintype "power_in"))
      (node (ref "U10") (pin "P9") (pinfunction "VSS_P9") (pintype "power_in"))
      (node (ref "U10") (pin "T1") (pinfunction "VSS_T1") (pintype "power_in"))
      (node (ref "U10") (pin "T9") (pinfunction "VSS_T9") (pintype "power_in"))
      (node (ref "U9") (pin "A9") (pinfunction "VSS_A9") (pintype "power_in"))
      (node (ref "U9") (pin "B1") (pinfunction "VSSQ_B1") (pintype "power_in"))
      (node (ref "U9") (pin "B3") (pinfunction "VSS_B3") (pintype "power_in"))
      (node (ref "U9") (pin "B9") (pinfunction "VSSQ_B9") (pintype "power_in"))
      (node (ref "U9") (pin "D1") (pinfunction "VSSQ_D1") (pintype "power_in"))
      (node (ref "U9") (pin "D8") (pinfunction "VSSQ_D8") (pintype "power_in"))
      (node (ref "U9") (pin "E1") (pinfunction "VSS_E1") (pintype "power_in"))
      (node (ref "U9") (pin "E2") (pinfunction "VSSQ_E2") (pintype "power_in"))
      (node (ref "U9") (pin "E8") (pinfunction "VSSQ_E8") (pintype "power_in"))
      (node (ref "U9") (pin "F9") (pinfunction "VSSQ_F9") (pintype "power_in"))
      (node (ref "U9") (pin "G1") (pinfunction "VSSQ_G1") (pintype "power_in"))
      (node (ref "U9") (pin "G8") (pinfunction "VSS_G8") (pintype "power_in"))
      (node (ref "U9") (pin "G9") (pinfunction "VSSQ_G9") (pintype "power_in"))
      (node (ref "U9") (pin "J2") (pinfunction "VSS_J2") (pintype "power_in"))
      (node (ref "U9") (pin "J8") (pinfunction "VSS_J8") (pintype "power_in"))
      (node (ref "U9") (pin "M1") (pinfunction "VSS_M1") (pintype "power_in"))
      (node (ref "U9") (pin "M9") (pinfunction "VSS_M9") (pintype "power_in"))
      (node (ref "U9") (pin "P1") (pinfunction "VSS_P1") (pintype "power_in"))
      (node (ref "U9") (pin "P9") (pinfunction "VSS_P9") (pintype "power_in"))
      (node (ref "U9") (pin "T1") (pinfunction "VSS_T1") (pintype "power_in"))
      (node (ref "U9") (pin "T9") (pinfunction "VSS_T9") (pintype "power_in"))
    )
    (net (code "79") (name "VCCO_PS_DDR") (class "Default")
      (node (ref "U10") (pin "A1") (pinfunction "VDDQ_A1") (pintype "power_in"))
      (node (ref "U10") (pin "A8") (pinfunction "VDDQ_A8") (pintype "power_in"))
      (node (ref "U10") (pin "B2") (pinfunction "VDD_B2") (pintype "power_in"))
      (node (ref "U10") (pin "C1") (pinfunction "VDDQ_C1") (pintype "power_in"))
      (node (ref "U10") (pin "C9") (pinfunction "VDDQ_C9") (pintype "power_in"))
      (node (ref "U10") (pin "D2") (pinfunction "VDDQ_D2") (pintype "power_in"))
      (node (ref "U10") (pin "D9") (pinfunction "VDD_D9") (pintype "power_in"))
      (node (ref "U10") (pin "E9") (pinfunction "VDDQ_E9") (pintype "power_in"))
      (node (ref "U10") (pin "F1") (pinfunction "VDDQ_F1") (pintype "power_in"))
      (node (ref "U10") (pin "G7") (pinfunction "VDD_G7") (pintype "power_in"))
      (node (ref "U10") (pin "H2") (pinfunction "VDDQ_H2") (pintype "power_in"))
      (node (ref "U10") (pin "H9") (pinfunction "VDDQ_H9") (pintype "power_in"))
      (node (ref "U10") (pin "K2") (pinfunction "VDD_K2") (pintype "power_in"))
      (node (ref "U10") (pin "K8") (pinfunction "VDD_K8") (pintype "power_in"))
      (node (ref "U10") (pin "N1") (pinfunction "VDD_N1") (pintype "power_in"))
      (node (ref "U10") (pin "N9") (pinfunction "VDD_N9") (pintype "power_in"))
      (node (ref "U10") (pin "R1") (pinfunction "VDD_R1") (pintype "power_in"))
      (node (ref "U10") (pin "R9") (pinfunction "VDD_R9") (pintype "power_in"))
      (node (ref "U9") (pin "A1") (pinfunction "VDDQ_A1") (pintype "power_in"))
      (node (ref "U9") (pin "A8") (pinfunction "VDDQ_A8") (pintype "power_in"))
      (node (ref "U9") (pin "B2") (pinfunction "VDD_B2") (pintype "power_in"))
      (node (ref "U9") (pin "C1") (pinfunction "VDDQ_C1") (pintype "power_in"))
      (node (ref "U9") (pin "C9") (pinfunction "VDDQ_C9") (pintype "power_in"))
      (node (ref "U9") (pin "D2") (pinfunction "VDDQ_D2") (pintype "power_in"))
      (node (ref "U9") (pin "D9") (pinfunction "VDD_D9") (pintype "power_in"))
      (node (ref "U9") (pin "E9") (pinfunction "VDDQ_E9") (pintype "power_in"))
      (node (ref "U9") (pin "F1") (pinfunction "VDDQ_F1") (pintype "power_in"))
      (node (ref "U9") (pin "G7") (pinfunction "VDD_G7") (pintype "power_in"))
      (node (ref "U9") (pin "H2") (pinfunction "VDDQ_H2") (pintype "power_in"))
      (node (ref "U9") (pin "H9") (pinfunction "VDDQ_H9") (pintype "power_in"))
      (node (ref "U9") (pin "K2") (pinfunction "VDD_K2") (pintype "power_in"))
      (node (ref "U9") (pin "K8") (pinfunction "VDD_K8") (pintype "power_in"))
      (node (ref "U9") (pin "N1") (pinfunction "VDD_N1") (pintype "power_in"))
      (node (ref "U9") (pin "N9") (pinfunction "VDD_N9") (pintype "power_in"))
      (node (ref "U9") (pin "R1") (pinfunction "VDD_R1") (pintype "power_in"))
      (node (ref "U9") (pin "R9") (pinfunction "VDD_R9") (pintype "power_in"))
    )
    (net (code "80") (name "VTT_PS_DDR") (class "Default")
      (node (ref "C28") (pin "2") (pinfunction "2_2") (pintype "passive"))
      (node (ref "C29") (pin "2") (pinfunction "2_2") (pintype "passive"))
      (node (ref "C30") (pin "2") (pinfunction "2_2") (pintype "passive"))
      (node (ref "C31") (pin "2") (pinfunction "2_2") (pintype "passive"))
      (node (ref "C32") (pin "2") (pinfunction "2_2") (pintype "passive"))
      (node (ref "C33") (pin "2") (pinfunction "2_2") (pintype "passive"))
      (node (ref "C34") (pin "2") (pinfunction "2_2") (pintype "passive"))
      (node (ref "C35") (pin "2") (pinfunction "2_2") (pintype "passive"))
      (node (ref "R62") (pin "1") (pinfunction "1_1") (pintype "passive"))
      (node (ref "R63") (pin "1") (pinfunction "1_1") (pintype "passive"))
      (node (ref "R64") (pin "1") (pinfunction "1_1") (pintype "passive"))
      (node (ref "R65") (pin "1") (pinfunction "1_1") (pintype "passive"))
      (node (ref "R66") (pin "1") (pinfunction "1_1") (pintype "passive"))
      (node (ref "R67") (pin "1") (pinfunction "1_1") (pintype "passive"))
      (node (ref "R68") (pin "1") (pinfunction "1_1") (pintype "passive"))
      (node (ref "R69") (pin "1") (pinfunction "1_1") (pintype "passive"))
      (node (ref "R70") (pin "1") (pinfunction "1_1") (pintype "passive"))
      (node (ref "R71") (pin "1") (pinfunction "1_1") (pintype "passive"))
      (node (ref "R72") (pin "1") (pinfunction "1_1") (pintype "passive"))
      (node (ref "R73") (pin "1") (pinfunction "1_1") (pintype "passive"))
      (node (ref "R74") (pin "1") (pinfunction "1_1") (pintype "passive"))
      (node (ref "R75") (pin "1") (pinfunction "1_1") (pintype "passive"))
      (node (ref "R76") (pin "1") (pinfunction "1_1") (pintype "passive"))
      (node (ref "R77") (pin "1") (pinfunction "1_1") (pintype "passive"))
      (node (ref "R78") (pin "1") (pinfunction "1_1") (pintype "passive"))
      (node (ref "R79") (pin "1") (pinfunction "1_1") (pintype "passive"))
      (node (ref "R80") (pin "1") (pinfunction "1_1") (pintype "passive"))
      (node (ref "R81") (pin "1") (pinfunction "1_1") (pintype "passive"))
      (node (ref "R82") (pin "1") (pinfunction "1_1") (pintype "passive"))
      (node (ref "R83") (pin "1") (pinfunction "1_1") (pintype "passive"))
      (node (ref "R84") (pin "1") (pinfunction "1_1") (pintype "passive"))
      (node (ref "R85") (pin "1") (pinfunction "1_1") (pintype "passive"))
    )
    (net (code "81") (name "VTT_PS_REF") (class "Default")
      (node (ref "C26") (pin "2") (pinfunction "2_2") (pintype "passive"))
      (node (ref "C27") (pin "2") (pinfunction "2_2") (pintype "passive"))
      (node (ref "U10") (pin "H1") (pinfunction "VREFDQ_H1") (pintype "power_in"))
      (node (ref "U10") (pin "M8") (pinfunction "VREFCA_M8") (pintype "power_in"))
      (node (ref "U9") (pin "H1") (pinfunction "VREFDQ_H1") (pintype "power_in"))
      (node (ref "U9") (pin "M8") (pinfunction "VREFCA_M8") (pintype "power_in"))
    )
    (net (code "82") (name "unconnected-(U9A-NC-PadJ1)") (class "Default")
      (node (ref "U9") (pin "J1") (pinfunction "NC_J1") (pintype "passive+no_connect"))
    )
    (net (code "83") (name "unconnected-(U9A-NC-PadJ9)") (class "Default")
      (node (ref "U9") (pin "J9") (pinfunction "NC_J9") (pintype "passive+no_connect"))
    )
    (net (code "84") (name "unconnected-(U9A-NC-PadL1)") (class "Default")
      (node (ref "U9") (pin "L1") (pinfunction "NC_L1") (pintype "passive+no_connect"))
    )
    (net (code "85") (name "unconnected-(U9A-NC-PadL9)") (class "Default")
      (node (ref "U9") (pin "L9") (pinfunction "NC_L9") (pintype "passive+no_connect"))
    )
    (net (code "86") (name "unconnected-(U9A-NC-PadM7)") (class "Default")
      (node (ref "U9") (pin "M7") (pinfunction "NC_M7") (pintype "passive+no_connect"))
    )
    (net (code "87") (name "unconnected-(U10A-NC-PadJ1)") (class "Default")
      (node (ref "U10") (pin "J1") (pinfunction "NC_J1") (pintype "passive+no_connect"))
    )
    (net (code "88") (name "unconnected-(U10A-NC-PadJ9)") (class "Default")
      (node (ref "U10") (pin "J9") (pinfunction "NC_J9") (pintype "passive+no_connect"))
    )
    (net (code "89") (name "unconnected-(U10A-NC-PadL1)") (class "Default")
      (node (ref "U10") (pin "L1") (pinfunction "NC_L1") (pintype "passive+no_connect"))
    )
    (net (code "90") (name "unconnected-(U10A-NC-PadL9)") (class "Default")
      (node (ref "U10") (pin "L9") (pinfunction "NC_L9") (pintype "passive+no_connect"))
    )
    (net (code "91") (name "unconnected-(U10A-NC-PadM7)") (class "Default")
      (node (ref "U10") (pin "M7") (pinfunction "NC_M7") (pintype "passive+no_connect"))
    )
  )
)
